# Motor_Driver_HIP4082_Board_V1_1.net
KiCad netlist of a schematic drawn in Altium Designer
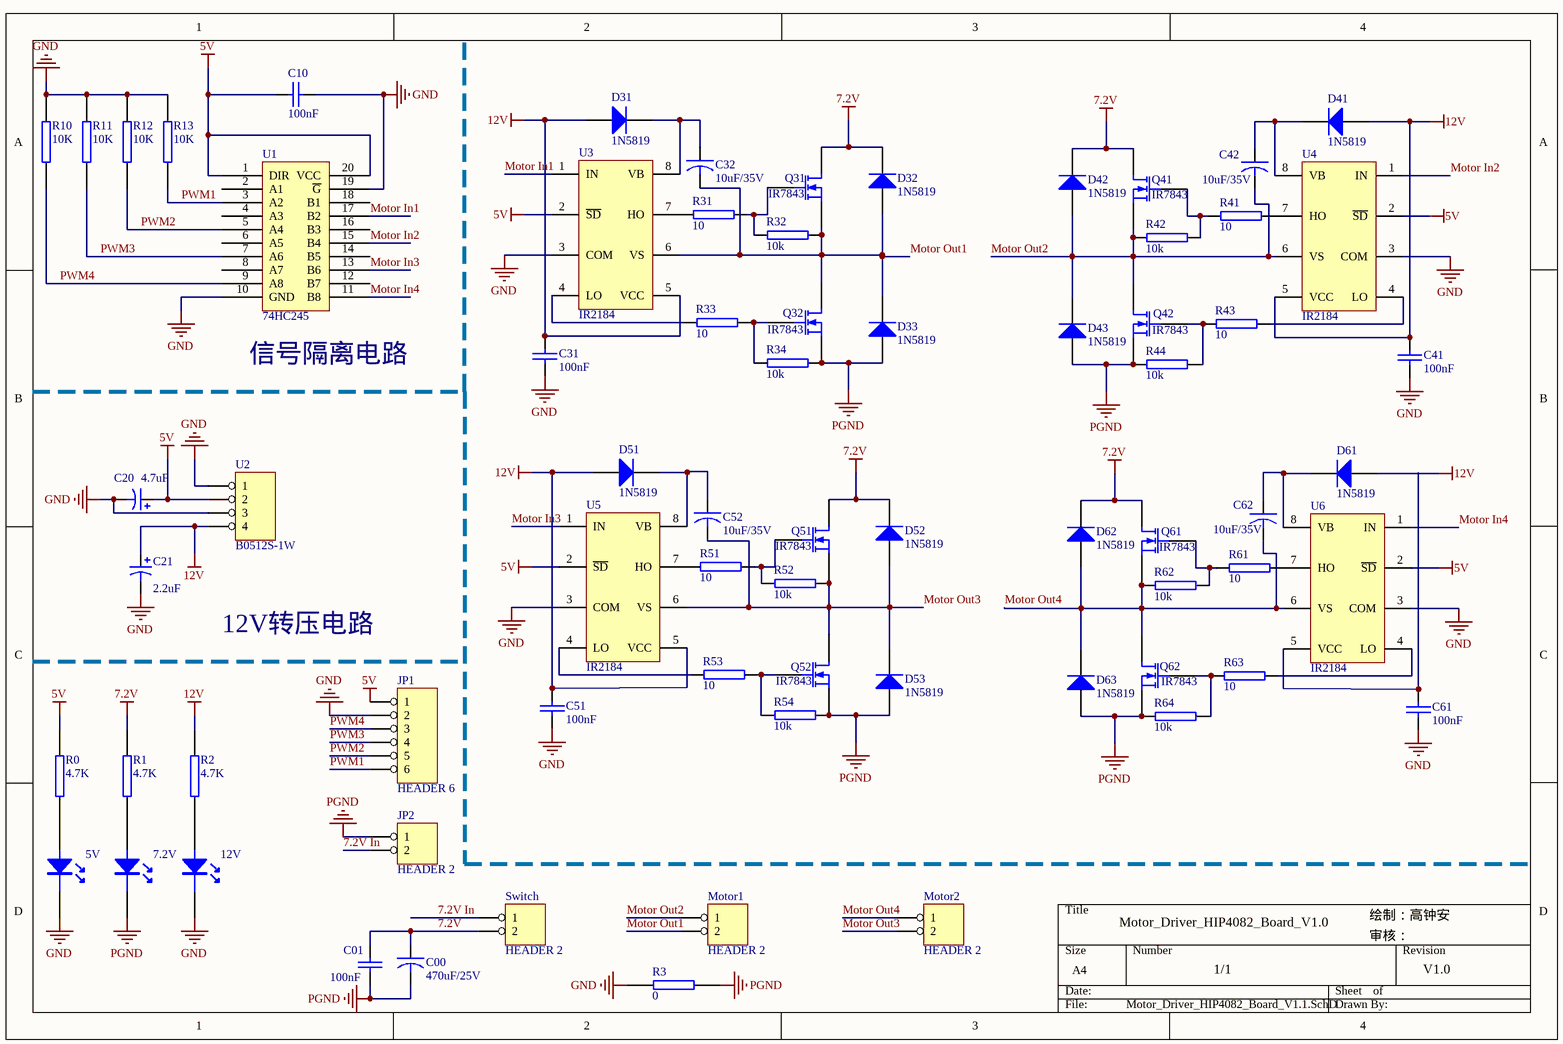
[diagram p0: Motor_Driver_HIP4082_Board_V1.1.SchDoc]

(export (version "E")
  (design (tool "Eeschema 10.0.6"))
  (components
    (comp (ref "5V") (value "~") (footprint "0805_LED_S1") (libsource (lib "Protel99Lib_SCH") (part "LED")))
    (comp (ref "7.2V") (value "~") (footprint "0805_LED_S1") (libsource (lib "Protel99Lib_SCH") (part "LED")))
    (comp (ref "12V") (value "~") (footprint "0805_LED_S1") (libsource (lib "Protel99Lib_SCH") (part "LED")))
    (comp (ref "C00")
      (value "470uF/25V")
      (footprint "RB.2/.4")
      (description "Capacitor")
      (libsource (lib "Protel99Lib_SCH") (part "CAPACITOR"))
    )
    (comp (ref "C01")
      (value "100nF")
      (footprint "0805C")
      (description "Capacitor")
      (libsource (lib "Protel99Lib_SCH") (part "CAP"))
    )
    (comp (ref "C10")
      (value "100nF")
      (footprint "0603_C")
      (description "Capacitor")
      (libsource (lib "Protel99Lib_SCH") (part "CAP"))
    )
    (comp (ref "C20")
      (value "4.7uF")
      (footprint "3528")
      (description "Polarized Capacitor (Surface Mount)")
      (fields (field (name "PUBLISHER") "Altium Limited"))
      (libsource (lib "Miscellaneous Devices") (part "Cap Pol3"))
    )
    (comp (ref "C21")
      (value "2.2uF")
      (footprint "3528")
      (description "Polarized Capacitor (Surface Mount)")
      (fields (field (name "PUBLISHER") "Altium Limited"))
      (libsource (lib "Miscellaneous Devices") (part "Cap Pol3"))
    )
    (comp (ref "C31")
      (value "100nF")
      (footprint "0805C")
      (description "Capacitor")
      (libsource (lib "Motor_Driver_IR2184") (part "CAP"))
    )
    (comp (ref "C32")
      (value "10uF/35V")
      (footprint "3528")
      (description "Capacitor")
      (libsource (lib "") (part "CAPACITOR_1"))
    )
    (comp (ref "C41")
      (value "100nF")
      (footprint "0805C")
      (description "Capacitor")
      (libsource (lib "Motor_Driver_IR2184") (part "CAP"))
    )
    (comp (ref "C42")
      (value "10uF/35V")
      (footprint "3528")
      (description "Capacitor")
      (libsource (lib "Motor_Driver_IR2184") (part "CAPACITOR"))
    )
    (comp (ref "C51")
      (value "100nF")
      (footprint "0805C")
      (description "Capacitor")
      (libsource (lib "Motor_Driver_IR2184") (part "CAP"))
    )
    (comp (ref "C52")
      (value "10uF/35V")
      (footprint "3528")
      (description "Capacitor")
      (libsource (lib "") (part "CAPACITOR_1"))
    )
    (comp (ref "C61")
      (value "100nF")
      (footprint "0805C")
      (description "Capacitor")
      (libsource (lib "Motor_Driver_IR2184") (part "CAP"))
    )
    (comp (ref "C62")
      (value "10uF/35V")
      (footprint "3528")
      (description "Capacitor")
      (libsource (lib "Motor_Driver_IR2184") (part "CAPACITOR"))
    )
    (comp (ref "D31")
      (value "1N5819")
      (footprint "3528")
      (description "Default Diode")
      (fields (field (name "PUBLISHER") "Altium Limited"))
      (libsource (lib "Motor_Driver_IR2184") (part "Diode"))
    )
    (comp (ref "D32")
      (value "1N5819")
      (footprint "3528")
      (description "Default Diode")
      (fields (field (name "PUBLISHER") "Altium Limited"))
      (libsource (lib "Motor_Driver_IR2184") (part "Diode"))
    )
    (comp (ref "D33")
      (value "1N5819")
      (footprint "3528")
      (description "Default Diode")
      (fields (field (name "PUBLISHER") "Altium Limited"))
      (libsource (lib "Motor_Driver_IR2184") (part "Diode"))
    )
    (comp (ref "D41")
      (value "1N5819")
      (footprint "3528")
      (description "Default Diode")
      (fields (field (name "PUBLISHER") "Altium Limited"))
      (libsource (lib "Motor_Driver_IR2184") (part "Diode"))
    )
    (comp (ref "D42")
      (value "1N5819")
      (footprint "3528")
      (description "Default Diode")
      (fields (field (name "PUBLISHER") "Altium Limited"))
      (libsource (lib "Motor_Driver_IR2184") (part "Diode"))
    )
    (comp (ref "D43")
      (value "1N5819")
      (footprint "3528")
      (description "Default Diode")
      (fields (field (name "PUBLISHER") "Altium Limited"))
      (libsource (lib "Motor_Driver_IR2184") (part "Diode"))
    )
    (comp (ref "D51")
      (value "1N5819")
      (footprint "3528")
      (description "Default Diode")
      (fields (field (name "PUBLISHER") "Altium Limited"))
      (libsource (lib "Motor_Driver_IR2184") (part "Diode"))
    )
    (comp (ref "D52")
      (value "1N5819")
      (footprint "3528")
      (description "Default Diode")
      (fields (field (name "PUBLISHER") "Altium Limited"))
      (libsource (lib "Motor_Driver_IR2184") (part "Diode"))
    )
    (comp (ref "D53")
      (value "1N5819")
      (footprint "3528")
      (description "Default Diode")
      (fields (field (name "PUBLISHER") "Altium Limited"))
      (libsource (lib "Motor_Driver_IR2184") (part "Diode"))
    )
    (comp (ref "D61")
      (value "1N5819")
      (footprint "3528")
      (description "Default Diode")
      (fields (field (name "PUBLISHER") "Altium Limited"))
      (libsource (lib "Motor_Driver_IR2184") (part "Diode"))
    )
    (comp (ref "D62")
      (value "1N5819")
      (footprint "3528")
      (description "Default Diode")
      (fields (field (name "PUBLISHER") "Altium Limited"))
      (libsource (lib "Motor_Driver_IR2184") (part "Diode"))
    )
    (comp (ref "D63")
      (value "1N5819")
      (footprint "3528")
      (description "Default Diode")
      (fields (field (name "PUBLISHER") "Altium Limited"))
      (libsource (lib "Motor_Driver_IR2184") (part "Diode"))
    )
    (comp (ref "JP1")
      (value "HEADER 6")
      (footprint "SIP6N")
      (libsource (lib "Protel99Lib_SCH") (part "HEADER 6"))
    )
    (comp (ref "JP2")
      (value "HEADER 2")
      (footprint "KF301-2P")
      (libsource (lib "Protel99Lib_SCH") (part "HEADER 2"))
    )
    (comp (ref "Motor1")
      (value "HEADER 2")
      (footprint "KF301-2P")
      (libsource (lib "Protel99Lib_SCH") (part "HEADER 2"))
    )
    (comp (ref "Motor2")
      (value "HEADER 2")
      (footprint "KF301-2P")
      (libsource (lib "Protel99Lib_SCH") (part "HEADER 2"))
    )
    (comp (ref "Q31")
      (value "IR7843")
      (footprint "TPH1R403")
      (description "N-Channel MOSFET")
      (fields (field (name "PUBLISHER") "Altium Limited"))
      (libsource (lib "Motor_Driver_IR2184") (part "MOSFET-N"))
    )
    (comp (ref "Q32")
      (value "IR7843")
      (footprint "TPH1R403")
      (description "N-Channel MOSFET")
      (fields (field (name "PUBLISHER") "Altium Limited"))
      (libsource (lib "Motor_Driver_IR2184") (part "MOSFET-N"))
    )
    (comp (ref "Q41")
      (value "IR7843")
      (footprint "TPH1R403")
      (description "N-Channel MOSFET")
      (fields (field (name "PUBLISHER") "Altium Limited"))
      (libsource (lib "Motor_Driver_IR2184") (part "MOSFET-N"))
    )
    (comp (ref "Q42")
      (value "IR7843")
      (footprint "TPH1R403")
      (description "N-Channel MOSFET")
      (fields (field (name "PUBLISHER") "Altium Limited"))
      (libsource (lib "Motor_Driver_IR2184") (part "MOSFET-N"))
    )
    (comp (ref "Q51")
      (value "IR7843")
      (footprint "TPH1R403")
      (description "N-Channel MOSFET")
      (fields (field (name "PUBLISHER") "Altium Limited"))
      (libsource (lib "Motor_Driver_IR2184") (part "MOSFET-N"))
    )
    (comp (ref "Q52")
      (value "IR7843")
      (footprint "TPH1R403")
      (description "N-Channel MOSFET")
      (fields (field (name "PUBLISHER") "Altium Limited"))
      (libsource (lib "Motor_Driver_IR2184") (part "MOSFET-N"))
    )
    (comp (ref "Q61")
      (value "IR7843")
      (footprint "TPH1R403")
      (description "N-Channel MOSFET")
      (fields (field (name "PUBLISHER") "Altium Limited"))
      (libsource (lib "Motor_Driver_IR2184") (part "MOSFET-N"))
    )
    (comp (ref "Q62")
      (value "IR7843")
      (footprint "TPH1R403")
      (description "N-Channel MOSFET")
      (fields (field (name "PUBLISHER") "Altium Limited"))
      (libsource (lib "Motor_Driver_IR2184") (part "MOSFET-N"))
    )
    (comp (ref "R0") (value "4.7K") (footprint "0603_R") (libsource (lib "Protel99Lib_SCH") (part "RES2")))
    (comp (ref "R1") (value "4.7K") (footprint "0603_R") (libsource (lib "Protel99Lib_SCH") (part "RES2")))
    (comp (ref "R2") (value "4.7K") (footprint "0603_R") (libsource (lib "Protel99Lib_SCH") (part "RES2")))
    (comp (ref "R3") (value "0") (footprint "0805") (libsource (lib "Protel99Lib_SCH") (part "RES2")))
    (comp (ref "R10") (value "10K") (footprint "0603_R") (libsource (lib "") (part "RES2_1")))
    (comp (ref "R11") (value "10K") (footprint "0603_R") (libsource (lib "") (part "RES2_1")))
    (comp (ref "R12") (value "10K") (footprint "0603_R") (libsource (lib "") (part "RES2_1")))
    (comp (ref "R13") (value "10K") (footprint "0603_R") (libsource (lib "") (part "RES2_1")))
    (comp (ref "R31") (value "10") (footprint "0805") (libsource (lib "Motor_Driver_IR2184") (part "RES2_1")))
    (comp (ref "R32")
      (value "10k")
      (footprint "0805")
      (libsource (lib "Motor_Driver_IR2184") (part "RES2_1"))
    )
    (comp (ref "R33") (value "10") (footprint "0805") (libsource (lib "Motor_Driver_IR2184") (part "RES2_1")))
    (comp (ref "R34")
      (value "10k")
      (footprint "0805")
      (libsource (lib "Motor_Driver_IR2184") (part "RES2_1"))
    )
    (comp (ref "R41") (value "10") (footprint "0805") (libsource (lib "Motor_Driver_IR2184") (part "RES2_1")))
    (comp (ref "R42")
      (value "10k")
      (footprint "0805")
      (libsource (lib "Motor_Driver_IR2184") (part "RES2_1"))
    )
    (comp (ref "R43") (value "10") (footprint "0805") (libsource (lib "Motor_Driver_IR2184") (part "RES2_1")))
    (comp (ref "R44")
      (value "10k")
      (footprint "0805")
      (libsource (lib "Motor_Driver_IR2184") (part "RES2_1"))
    )
    (comp (ref "R51") (value "10") (footprint "0805") (libsource (lib "Motor_Driver_IR2184") (part "RES2_1")))
    (comp (ref "R52")
      (value "10k")
      (footprint "0805")
      (libsource (lib "Motor_Driver_IR2184") (part "RES2_1"))
    )
    (comp (ref "R53") (value "10") (footprint "0805") (libsource (lib "Motor_Driver_IR2184") (part "RES2_1")))
    (comp (ref "R54")
      (value "10k")
      (footprint "0805")
      (libsource (lib "Motor_Driver_IR2184") (part "RES2_1"))
    )
    (comp (ref "R61") (value "10") (footprint "0805") (libsource (lib "Motor_Driver_IR2184") (part "RES2_1")))
    (comp (ref "R62")
      (value "10k")
      (footprint "0805")
      (libsource (lib "Motor_Driver_IR2184") (part "RES2_1"))
    )
    (comp (ref "R63") (value "10") (footprint "0805") (libsource (lib "Motor_Driver_IR2184") (part "RES2_1")))
    (comp (ref "R64")
      (value "10k")
      (footprint "0805")
      (libsource (lib "Motor_Driver_IR2184") (part "RES2_1"))
    )
    (comp (ref "Switch")
      (value "HEADER 2")
      (footprint "SWITCH-MINI")
      (libsource (lib "Protel99Lib_SCH") (part "HEADER 2"))
    )
    (comp (ref "U1") (value "74HC245") (footprint "SOP20") (libsource (lib "BaseLib_SCH") (part "74HC245")))
    (comp (ref "U2")
      (value "B0512S-1W")
      (footprint "SIP4_B_S-1W")
      (description "4 Pin Header")
      (libsource (lib "Protel99Lib_SCH") (part "4 HEADER"))
    )
    (comp (ref "U3")
      (value "IR2184")
      (footprint "SO-8")
      (libsource (lib "Motor_Driver_IR2184") (part "IR2184"))
    )
    (comp (ref "U4") (value "IR2184") (footprint "SO-8") (libsource (lib "") (part "IR2184_1")))
    (comp (ref "U5")
      (value "IR2184")
      (footprint "SO-8")
      (libsource (lib "Motor_Driver_IR2184") (part "IR2184"))
    )
    (comp (ref "U6") (value "IR2184") (footprint "SO-8") (libsource (lib "") (part "IR2184_1")))
  )
  (nets
    (net (code "1") (name "/7.2V In") (class "Default")
      (node (ref "JP2") (pin "2") (pinfunction "2_2") (pintype "passive"))
      (node (ref "Switch") (pin "1") (pinfunction "1_1") (pintype "passive"))
    )
    (net (code "2") (name "/Motor In1") (class "Default")
      (node (ref "U1") (pin "17") (pinfunction "B2_17") (pintype "passive"))
      (node (ref "U3") (pin "1") (pinfunction "IN_1") (pintype "passive"))
    )
    (net (code "3") (name "/Motor In2") (class "Default")
      (node (ref "U1") (pin "15") (pinfunction "B4_15") (pintype "passive"))
      (node (ref "U4") (pin "1") (pinfunction "IN_1") (pintype "passive"))
    )
    (net (code "4") (name "/Motor In3") (class "Default")
      (node (ref "U1") (pin "13") (pinfunction "B6_13") (pintype "passive"))
      (node (ref "U5") (pin "1") (pinfunction "IN_1") (pintype "passive"))
    )
    (net (code "5") (name "/Motor In4") (class "Default")
      (node (ref "U1") (pin "11") (pinfunction "B8_11") (pintype "passive"))
      (node (ref "U6") (pin "1") (pinfunction "IN_1") (pintype "passive"))
    )
    (net (code "6") (name "/Motor Out1") (class "Default")
      (node (ref "C32") (pin "2") (pinfunction "2_2") (pintype "passive"))
      (node (ref "D32") (pin "1") (pinfunction "A_1") (pintype "passive"))
      (node (ref "D33") (pin "2") (pinfunction "K_2") (pintype "passive"))
      (node (ref "Motor1") (pin "2") (pinfunction "2_2") (pintype "passive"))
      (node (ref "Q31") (pin "3") (pinfunction "S_3") (pintype "passive"))
      (node (ref "Q32") (pin "1") (pinfunction "D_1") (pintype "passive"))
      (node (ref "R32") (pin "1") (pinfunction "1_1") (pintype "passive"))
      (node (ref "U3") (pin "6") (pinfunction "VS_6") (pintype "passive"))
    )
    (net (code "7") (name "/Motor Out2") (class "Default")
      (node (ref "C42") (pin "2") (pinfunction "2_2") (pintype "passive"))
      (node (ref "D42") (pin "1") (pinfunction "A_1") (pintype "passive"))
      (node (ref "D43") (pin "2") (pinfunction "K_2") (pintype "passive"))
      (node (ref "Motor1") (pin "1") (pinfunction "1_1") (pintype "passive"))
      (node (ref "Q41") (pin "3") (pinfunction "S_3") (pintype "passive"))
      (node (ref "Q42") (pin "1") (pinfunction "D_1") (pintype "passive"))
      (node (ref "R42") (pin "2") (pinfunction "2_2") (pintype "passive"))
      (node (ref "U4") (pin "6") (pinfunction "VS_6") (pintype "passive"))
    )
    (net (code "8") (name "/Motor Out3") (class "Default")
      (node (ref "C52") (pin "2") (pinfunction "2_2") (pintype "passive"))
      (node (ref "D52") (pin "1") (pinfunction "A_1") (pintype "passive"))
      (node (ref "D53") (pin "2") (pinfunction "K_2") (pintype "passive"))
      (node (ref "Motor2") (pin "2") (pinfunction "2_2") (pintype "passive"))
      (node (ref "Q51") (pin "3") (pinfunction "S_3") (pintype "passive"))
      (node (ref "Q52") (pin "1") (pinfunction "D_1") (pintype "passive"))
      (node (ref "R52") (pin "1") (pinfunction "1_1") (pintype "passive"))
      (node (ref "U5") (pin "6") (pinfunction "VS_6") (pintype "passive"))
    )
    (net (code "9") (name "/Motor Out4") (class "Default")
      (node (ref "C62") (pin "2") (pinfunction "2_2") (pintype "passive"))
      (node (ref "D62") (pin "1") (pinfunction "A_1") (pintype "passive"))
      (node (ref "D63") (pin "2") (pinfunction "K_2") (pintype "passive"))
      (node (ref "Motor2") (pin "1") (pinfunction "1_1") (pintype "passive"))
      (node (ref "Q61") (pin "3") (pinfunction "S_3") (pintype "passive"))
      (node (ref "Q62") (pin "1") (pinfunction "D_1") (pintype "passive"))
      (node (ref "R62") (pin "2") (pinfunction "2_2") (pintype "passive"))
      (node (ref "U6") (pin "6") (pinfunction "VS_6") (pintype "passive"))
    )
    (net (code "10") (name "/PWM1") (class "Default")
      (node (ref "JP1") (pin "6") (pinfunction "6_6") (pintype "passive"))
      (node (ref "R13") (pin "1") (pinfunction "1_1") (pintype "passive"))
      (node (ref "U1") (pin "3") (pinfunction "A2_3") (pintype "passive"))
    )
    (net (code "11") (name "/PWM2") (class "Default")
      (node (ref "JP1") (pin "5") (pinfunction "5_5") (pintype "passive"))
      (node (ref "R12") (pin "1") (pinfunction "1_1") (pintype "passive"))
      (node (ref "U1") (pin "5") (pinfunction "A4_5") (pintype "passive"))
    )
    (net (code "12") (name "/PWM3") (class "Default")
      (node (ref "JP1") (pin "4") (pinfunction "4_4") (pintype "passive"))
      (node (ref "R11") (pin "2") (pinfunction "2_2") (pintype "passive"))
      (node (ref "U1") (pin "7") (pinfunction "A6_7") (pintype "passive"))
    )
    (net (code "13") (name "/PWM4") (class "Default")
      (node (ref "JP1") (pin "3") (pinfunction "3_3") (pintype "passive"))
      (node (ref "R10") (pin "1") (pinfunction "1_1") (pintype "passive"))
      (node (ref "U1") (pin "9") (pinfunction "A8_9") (pintype "passive"))
    )
    (net (code "14") (name "5V") (class "Default")
      (node (ref "C10") (pin "1") (pinfunction "1_1") (pintype "passive"))
      (node (ref "C20") (pin "1") (pinfunction "1_1") (pintype "passive"))
      (node (ref "JP1") (pin "1") (pinfunction "1_1") (pintype "passive"))
      (node (ref "R0") (pin "2") (pinfunction "2_2") (pintype "passive"))
      (node (ref "U1") (pin "1") (pinfunction "DIR_1") (pintype "passive"))
      (node (ref "U1") (pin "20") (pinfunction "VCC_20") (pintype "passive"))
      (node (ref "U2") (pin "2") (pinfunction "2_2") (pintype "passive"))
      (node (ref "U3") (pin "2") (pinfunction "~{SD}_2") (pintype "passive"))
      (node (ref "U4") (pin "2") (pinfunction "~{SD}_2") (pintype "passive"))
      (node (ref "U5") (pin "2") (pinfunction "~{SD}_2") (pintype "passive"))
      (node (ref "U6") (pin "2") (pinfunction "~{SD}_2") (pintype "passive"))
    )
    (net (code "15") (name "7.2V") (class "Default")
      (node (ref "C00") (pin "1") (pinfunction "1_1") (pintype "passive"))
      (node (ref "C01") (pin "2") (pinfunction "2_2") (pintype "passive"))
      (node (ref "D32") (pin "2") (pinfunction "K_2") (pintype "passive"))
      (node (ref "D42") (pin "2") (pinfunction "K_2") (pintype "passive"))
      (node (ref "D52") (pin "2") (pinfunction "K_2") (pintype "passive"))
      (node (ref "D62") (pin "2") (pinfunction "K_2") (pintype "passive"))
      (node (ref "Q31") (pin "1") (pinfunction "D_1") (pintype "passive"))
      (node (ref "Q41") (pin "1") (pinfunction "D_1") (pintype "passive"))
      (node (ref "Q51") (pin "1") (pinfunction "D_1") (pintype "passive"))
      (node (ref "Q61") (pin "1") (pinfunction "D_1") (pintype "passive"))
      (node (ref "R1") (pin "2") (pinfunction "2_2") (pintype "passive"))
      (node (ref "Switch") (pin "2") (pinfunction "2_2") (pintype "passive"))
    )
    (net (code "16") (name "12V") (class "Default")
      (node (ref "C21") (pin "1") (pinfunction "1_1") (pintype "passive"))
      (node (ref "C31") (pin "1") (pinfunction "1_1") (pintype "passive"))
      (node (ref "C41") (pin "1") (pinfunction "1_1") (pintype "passive"))
      (node (ref "C51") (pin "1") (pinfunction "1_1") (pintype "passive"))
      (node (ref "D31") (pin "1") (pinfunction "A_1") (pintype "passive"))
      (node (ref "D41") (pin "1") (pinfunction "A_1") (pintype "passive"))
      (node (ref "D51") (pin "1") (pinfunction "A_1") (pintype "passive"))
      (node (ref "D61") (pin "1") (pinfunction "A_1") (pintype "passive"))
      (node (ref "R2") (pin "2") (pinfunction "2_2") (pintype "passive"))
      (node (ref "U2") (pin "4") (pinfunction "4_4") (pintype "passive"))
      (node (ref "U3") (pin "5") (pinfunction "VCC_5") (pintype "passive"))
      (node (ref "U4") (pin "5") (pinfunction "VCC_5") (pintype "passive"))
      (node (ref "U5") (pin "5") (pinfunction "VCC_5") (pintype "passive"))
    )
    (net (code "17") (name "GND") (class "Default")
      (node (ref "12V") (pin "K") (pinfunction "2_K") (pintype "passive"))
      (node (ref "5V") (pin "K") (pinfunction "2_K") (pintype "passive"))
      (node (ref "C10") (pin "2") (pinfunction "2_2") (pintype "passive"))
      (node (ref "C20") (pin "2") (pinfunction "2_2") (pintype "passive"))
      (node (ref "C21") (pin "2") (pinfunction "2_2") (pintype "passive"))
      (node (ref "C31") (pin "2") (pinfunction "2_2") (pintype "passive"))
      (node (ref "C41") (pin "2") (pinfunction "2_2") (pintype "passive"))
      (node (ref "C51") (pin "2") (pinfunction "2_2") (pintype "passive"))
      (node (ref "C61") (pin "2") (pinfunction "2_2") (pintype "passive"))
      (node (ref "JP1") (pin "2") (pinfunction "2_2") (pintype "passive"))
      (node (ref "R10") (pin "2") (pinfunction "2_2") (pintype "passive"))
      (node (ref "R11") (pin "1") (pinfunction "1_1") (pintype "passive"))
      (node (ref "R12") (pin "2") (pinfunction "2_2") (pintype "passive"))
      (node (ref "R13") (pin "2") (pinfunction "2_2") (pintype "passive"))
      (node (ref "R3") (pin "2") (pinfunction "2_2") (pintype "passive"))
      (node (ref "U1") (pin "10") (pinfunction "GND_10") (pintype "passive"))
      (node (ref "U1") (pin "19") (pinfunction "~{G}_19") (pintype "passive"))
      (node (ref "U2") (pin "1") (pinfunction "1_1") (pintype "passive"))
      (node (ref "U2") (pin "3") (pinfunction "3_3") (pintype "passive"))
      (node (ref "U3") (pin "3") (pinfunction "COM_3") (pintype "passive"))
      (node (ref "U4") (pin "3") (pinfunction "COM_3") (pintype "passive"))
      (node (ref "U5") (pin "3") (pinfunction "COM_3") (pintype "passive"))
      (node (ref "U6") (pin "3") (pinfunction "COM_3") (pintype "passive"))
    )
    (net (code "18") (name "Net-(5V-1)") (class "Default")
      (node (ref "5V") (pin "A") (pinfunction "1_A") (pintype "passive"))
      (node (ref "R0") (pin "1") (pinfunction "1_1") (pintype "passive"))
    )
    (net (code "19") (name "Net-(7.2V-1)") (class "Default")
      (node (ref "7.2V") (pin "A") (pinfunction "1_A") (pintype "passive"))
      (node (ref "R1") (pin "1") (pinfunction "1_1") (pintype "passive"))
    )
    (net (code "20") (name "Net-(12V-1)") (class "Default")
      (node (ref "12V") (pin "A") (pinfunction "1_A") (pintype "passive"))
      (node (ref "R2") (pin "1") (pinfunction "1_1") (pintype "passive"))
    )
    (net (code "21") (name "Net-(D31-K)") (class "Default")
      (node (ref "C32") (pin "1") (pinfunction "1_1") (pintype "passive"))
      (node (ref "D31") (pin "2") (pinfunction "K_2") (pintype "passive"))
      (node (ref "U3") (pin "8") (pinfunction "VB_8") (pintype "passive"))
    )
    (net (code "22") (name "Net-(D41-K)") (class "Default")
      (node (ref "C42") (pin "1") (pinfunction "1_1") (pintype "passive"))
      (node (ref "D41") (pin "2") (pinfunction "K_2") (pintype "passive"))
      (node (ref "U4") (pin "8") (pinfunction "VB_8") (pintype "passive"))
    )
    (net (code "23") (name "Net-(D51-K)") (class "Default")
      (node (ref "C52") (pin "1") (pinfunction "1_1") (pintype "passive"))
      (node (ref "D51") (pin "2") (pinfunction "K_2") (pintype "passive"))
      (node (ref "U5") (pin "8") (pinfunction "VB_8") (pintype "passive"))
    )
    (net (code "24") (name "Net-(D61-K)") (class "Default")
      (node (ref "C62") (pin "1") (pinfunction "1_1") (pintype "passive"))
      (node (ref "D61") (pin "2") (pinfunction "K_2") (pintype "passive"))
      (node (ref "U6") (pin "8") (pinfunction "VB_8") (pintype "passive"))
    )
    (net (code "25") (name "Net-(Q31-G)") (class "Default")
      (node (ref "Q31") (pin "2") (pinfunction "G_2") (pintype "passive"))
      (node (ref "R31") (pin "2") (pinfunction "2_2") (pintype "passive"))
      (node (ref "R32") (pin "2") (pinfunction "2_2") (pintype "passive"))
    )
    (net (code "26") (name "Net-(Q32-G)") (class "Default")
      (node (ref "Q32") (pin "2") (pinfunction "G_2") (pintype "passive"))
      (node (ref "R33") (pin "2") (pinfunction "2_2") (pintype "passive"))
      (node (ref "R34") (pin "2") (pinfunction "2_2") (pintype "passive"))
    )
    (net (code "27") (name "Net-(Q41-G)") (class "Default")
      (node (ref "Q41") (pin "2") (pinfunction "G_2") (pintype "passive"))
      (node (ref "R41") (pin "2") (pinfunction "2_2") (pintype "passive"))
      (node (ref "R42") (pin "1") (pinfunction "1_1") (pintype "passive"))
    )
    (net (code "28") (name "Net-(Q42-G)") (class "Default")
      (node (ref "Q42") (pin "2") (pinfunction "G_2") (pintype "passive"))
      (node (ref "R43") (pin "2") (pinfunction "2_2") (pintype "passive"))
      (node (ref "R44") (pin "1") (pinfunction "1_1") (pintype "passive"))
    )
    (net (code "29") (name "Net-(Q51-G)") (class "Default")
      (node (ref "Q51") (pin "2") (pinfunction "G_2") (pintype "passive"))
      (node (ref "R51") (pin "2") (pinfunction "2_2") (pintype "passive"))
      (node (ref "R52") (pin "2") (pinfunction "2_2") (pintype "passive"))
    )
    (net (code "30") (name "Net-(Q52-G)") (class "Default")
      (node (ref "Q52") (pin "2") (pinfunction "G_2") (pintype "passive"))
      (node (ref "R53") (pin "2") (pinfunction "2_2") (pintype "passive"))
      (node (ref "R54") (pin "2") (pinfunction "2_2") (pintype "passive"))
    )
    (net (code "31") (name "Net-(Q61-G)") (class "Default")
      (node (ref "Q61") (pin "2") (pinfunction "G_2") (pintype "passive"))
      (node (ref "R61") (pin "2") (pinfunction "2_2") (pintype "passive"))
      (node (ref "R62") (pin "1") (pinfunction "1_1") (pintype "passive"))
    )
    (net (code "32") (name "Net-(Q62-G)") (class "Default")
      (node (ref "Q62") (pin "2") (pinfunction "G_2") (pintype "passive"))
      (node (ref "R63") (pin "2") (pinfunction "2_2") (pintype "passive"))
      (node (ref "R64") (pin "1") (pinfunction "1_1") (pintype "passive"))
    )
    (net (code "33") (name "Net-(U3-HO)") (class "Default")
      (node (ref "R31") (pin "1") (pinfunction "1_1") (pintype "passive"))
      (node (ref "U3") (pin "7") (pinfunction "HO_7") (pintype "passive"))
    )
    (net (code "34") (name "Net-(U3-LO)") (class "Default")
      (node (ref "R33") (pin "1") (pinfunction "1_1") (pintype "passive"))
      (node (ref "U3") (pin "4") (pinfunction "LO_4") (pintype "passive"))
    )
    (net (code "35") (name "Net-(U4-HO)") (class "Default")
      (node (ref "R41") (pin "1") (pinfunction "1_1") (pintype "passive"))
      (node (ref "U4") (pin "7") (pinfunction "HO_7") (pintype "passive"))
    )
    (net (code "36") (name "Net-(U4-LO)") (class "Default")
      (node (ref "R43") (pin "1") (pinfunction "1_1") (pintype "passive"))
      (node (ref "U4") (pin "4") (pinfunction "LO_4") (pintype "passive"))
    )
    (net (code "37") (name "Net-(U5-HO)") (class "Default")
      (node (ref "R51") (pin "1") (pinfunction "1_1") (pintype "passive"))
      (node (ref "U5") (pin "7") (pinfunction "HO_7") (pintype "passive"))
    )
    (net (code "38") (name "Net-(U5-LO)") (class "Default")
      (node (ref "R53") (pin "1") (pinfunction "1_1") (pintype "passive"))
      (node (ref "U5") (pin "4") (pinfunction "LO_4") (pintype "passive"))
    )
    (net (code "39") (name "Net-(U6-HO)") (class "Default")
      (node (ref "R61") (pin "1") (pinfunction "1_1") (pintype "passive"))
      (node (ref "U6") (pin "7") (pinfunction "HO_7") (pintype "passive"))
    )
    (net (code "40") (name "Net-(U6-LO)") (class "Default")
      (node (ref "R63") (pin "1") (pinfunction "1_1") (pintype "passive"))
      (node (ref "U6") (pin "4") (pinfunction "LO_4") (pintype "passive"))
    )
    (net (code "41") (name "Net-(U6-VCC)") (class "Default")
      (node (ref "C61") (pin "1") (pinfunction "1_1") (pintype "passive"))
      (node (ref "U6") (pin "5") (pinfunction "VCC_5") (pintype "passive"))
    )
    (net (code "42") (name "PGND") (class "Default")
      (node (ref "7.2V") (pin "K") (pinfunction "2_K") (pintype "passive"))
      (node (ref "C00") (pin "2") (pinfunction "2_2") (pintype "passive"))
      (node (ref "C01") (pin "1") (pinfunction "1_1") (pintype "passive"))
      (node (ref "D33") (pin "1") (pinfunction "A_1") (pintype "passive"))
      (node (ref "D43") (pin "1") (pinfunction "A_1") (pintype "passive"))
      (node (ref "D53") (pin "1") (pinfunction "A_1") (pintype "passive"))
      (node (ref "D63") (pin "1") (pinfunction "A_1") (pintype "passive"))
      (node (ref "JP2") (pin "1") (pinfunction "1_1") (pintype "passive"))
      (node (ref "Q32") (pin "3") (pinfunction "S_3") (pintype "passive"))
      (node (ref "Q42") (pin "3") (pinfunction "S_3") (pintype "passive"))
      (node (ref "Q52") (pin "3") (pinfunction "S_3") (pintype "passive"))
      (node (ref "Q62") (pin "3") (pinfunction "S_3") (pintype "passive"))
      (node (ref "R3") (pin "1") (pinfunction "1_1") (pintype "passive"))
      (node (ref "R34") (pin "1") (pinfunction "1_1") (pintype "passive"))
      (node (ref "R44") (pin "2") (pinfunction "2_2") (pintype "passive"))
      (node (ref "R54") (pin "1") (pinfunction "1_1") (pintype "passive"))
      (node (ref "R64") (pin "2") (pinfunction "2_2") (pintype "passive"))
    )
    (net (code "43") (name "unconnected-(U1-A1-Pad2)") (class "Default")
      (node (ref "U1") (pin "2") (pinfunction "A1_2") (pintype "passive"))
    )
    (net (code "44") (name "unconnected-(U1-A3-Pad4)") (class "Default")
      (node (ref "U1") (pin "4") (pinfunction "A3_4") (pintype "passive"))
    )
    (net (code "45") (name "unconnected-(U1-A5-Pad6)") (class "Default")
      (node (ref "U1") (pin "6") (pinfunction "A5_6") (pintype "passive"))
    )
    (net (code "46") (name "unconnected-(U1-A7-Pad8)") (class "Default")
      (node (ref "U1") (pin "8") (pinfunction "A7_8") (pintype "passive"))
    )
    (net (code "47") (name "unconnected-(U1-B1-Pad18)") (class "Default")
      (node (ref "U1") (pin "18") (pinfunction "B1_18") (pintype "passive"))
    )
    (net (code "48") (name "unconnected-(U1-B3-Pad16)") (class "Default")
      (node (ref "U1") (pin "16") (pinfunction "B3_16") (pintype "passive"))
    )
    (net (code "49") (name "unconnected-(U1-B5-Pad14)") (class "Default")
      (node (ref "U1") (pin "14") (pinfunction "B5_14") (pintype "passive"))
    )
    (net (code "50") (name "unconnected-(U1-B7-Pad12)") (class "Default")
      (node (ref "U1") (pin "12") (pinfunction "B7_12") (pintype "passive"))
    )
  )
)
